# Valve_with_oc.net
KiCad netlist of a schematic drawn in EAGLE
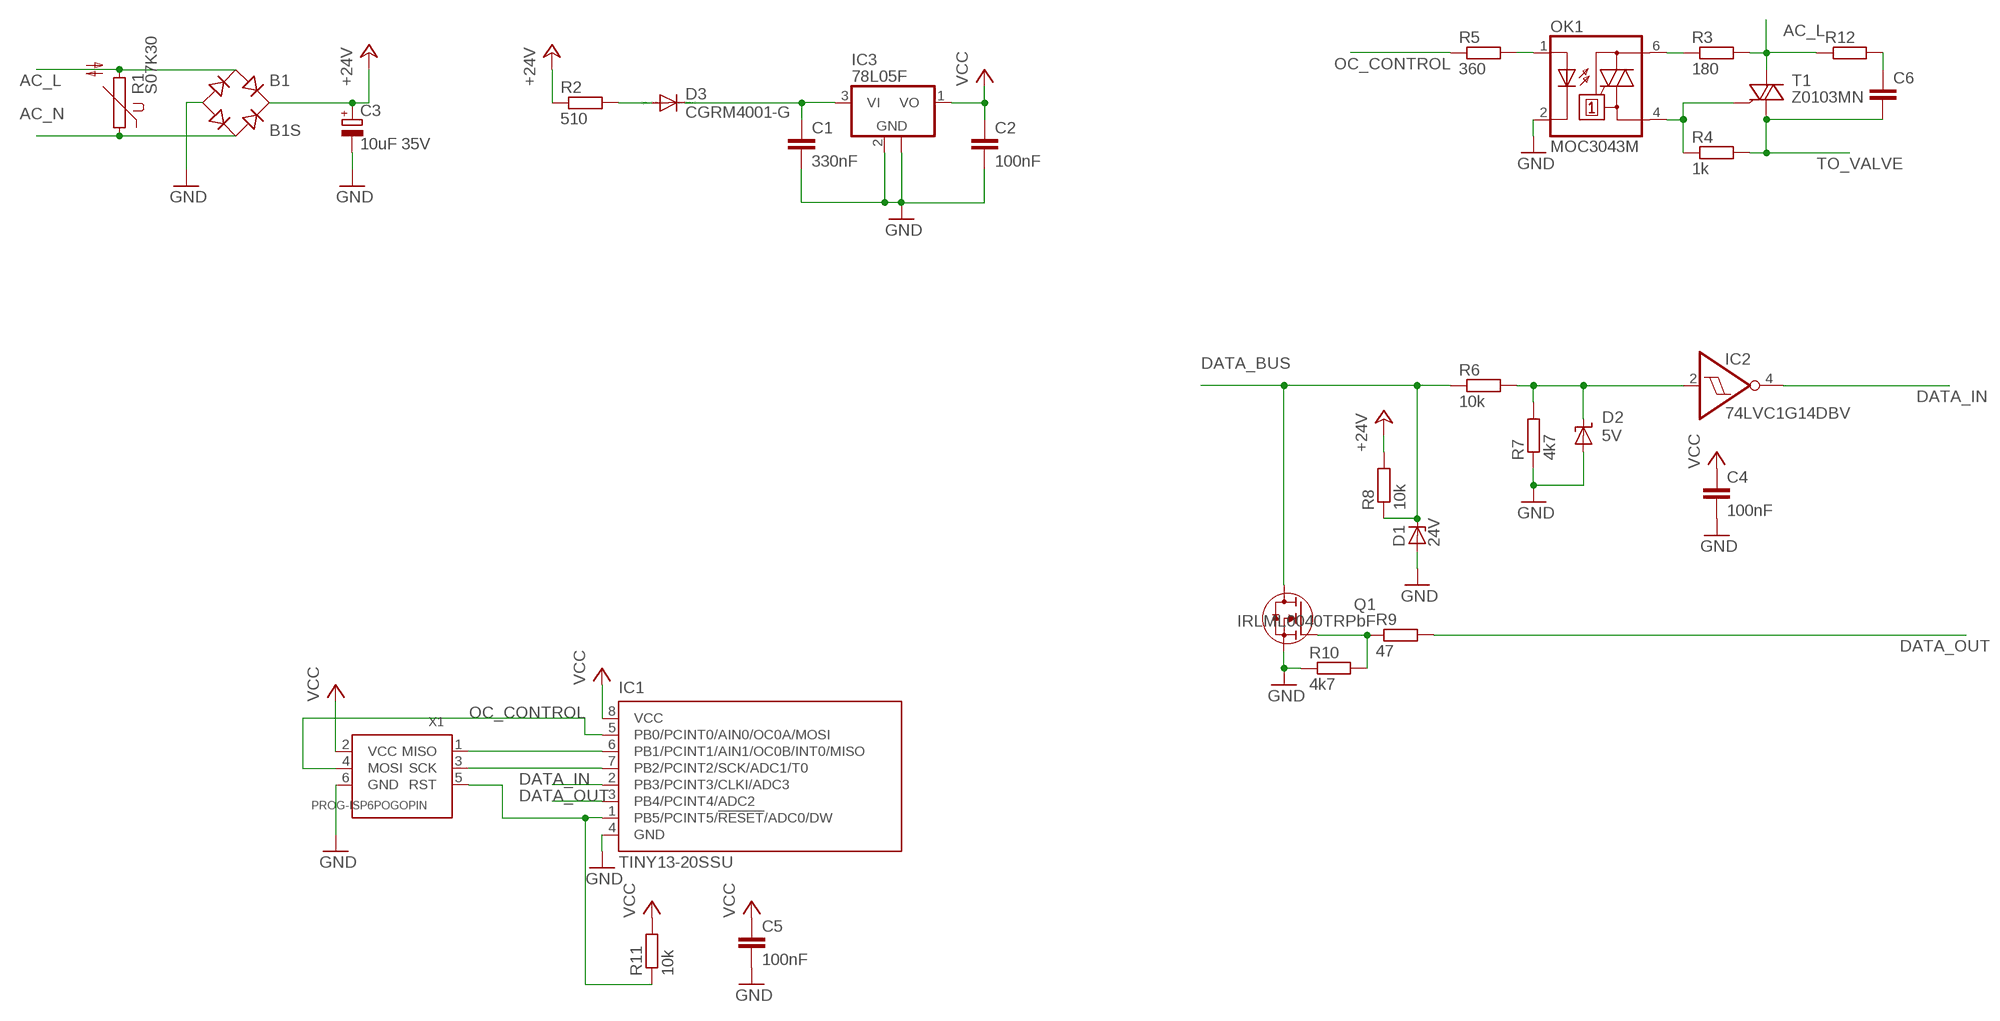
[diagram p0: schematic, sheet 1]

(export (version "E")
  (design (tool "Eeschema 10.0.6"))
  (components
    (comp (ref "B1")
      (value "B1S")
      (footprint "eagle-import:MBS")
      (libsource (lib "eagle-import") (part "BS1"))
    )
    (comp (ref "C1")
      (value "330nF")
      (footprint "eagle-import:C0805K")
      (libsource (lib "eagle-import") (part "C-EUC0805K"))
    )
    (comp (ref "C2")
      (value "100nF")
      (footprint "eagle-import:C0805K")
      (libsource (lib "eagle-import") (part "C-EUC0805K"))
    )
    (comp (ref "C3")
      (value "10uF 35V")
      (footprint "eagle-import:C_6032-28R")
      (libsource (lib "eagle-import") (part "CPOL-EUC/6032-28R"))
    )
    (comp (ref "C4")
      (value "100nF")
      (footprint "eagle-import:C0805K")
      (libsource (lib "eagle-import") (part "C-EUC0805K"))
    )
    (comp (ref "C5")
      (value "100nF")
      (footprint "eagle-import:C0805K")
      (libsource (lib "eagle-import") (part "C-EUC0805K"))
    )
    (comp (ref "C6")
      (value "C-EUC0805K")
      (footprint "eagle-import:C0805K")
      (libsource (lib "eagle-import") (part "C-EUC0805K"))
    )
    (comp (ref "D1")
      (value "24V")
      (footprint "eagle-import:SOT23")
      (libsource (lib "eagle-import") (part "ZENER-DIODESOT23"))
    )
    (comp (ref "D2")
      (value "5V")
      (footprint "eagle-import:SOD123")
      (libsource (lib "eagle-import") (part "ZENER"))
    )
    (comp (ref "D3")
      (value "CGRM4001-G")
      (footprint "eagle-import:SOD-123_MINI-SMA")
      (libsource (lib "eagle-import") (part "CGRM400-G1"))
    )
    (comp (ref "IC1")
      (value "TINY13-20SSU")
      (footprint "eagle-import:8S1")
      (fields (field (name "MPN") "ATTINY13-20SSU"))
      (libsource (lib "eagle-import") (part "TINY13SSU-20"))
    )
    (comp (ref "IC2")
      (value "74LVC1G14DBV")
      (footprint "eagle-import:SOT23-5")
      (libsource (lib "eagle-import") (part "741G14DBVLVC"))
    )
    (comp (ref "IC3")
      (value "78L05F")
      (footprint "eagle-import:SOT89")
      (libsource (lib "eagle-import") (part "78LF05"))
    )
    (comp (ref "OK1")
      (value "MOC3043M")
      (footprint "eagle-import:DIL06")
      (fields (field (name "MF") "FAIRCHILD SEMICONDUCTOR") (field (name "MPN") "MOC3043-M"))
      (libsource (lib "eagle-import") (part "MOC3043M"))
    )
    (comp (ref "Q1")
      (value "IRLML0040TRPbF")
      (footprint "eagle-import:SOT-23-GSD")
      (libsource (lib "eagle-import") (part "SI2302"))
    )
    (comp (ref "R1")
      (value "S07K30")
      (footprint "eagle-import:S07K40")
      (libsource (lib "eagle-import") (part "S07K40"))
    )
    (comp (ref "R2")
      (value "510")
      (footprint "eagle-import:R2512")
      (libsource (lib "eagle-import") (part "R-EU_R2512"))
    )
    (comp (ref "R3")
      (value "180")
      (footprint "eagle-import:R0805")
      (libsource (lib "eagle-import") (part "R-EU_R0805"))
    )
    (comp (ref "R4")
      (value "1k")
      (footprint "eagle-import:R0805")
      (libsource (lib "eagle-import") (part "R-EU_R0805"))
    )
    (comp (ref "R5")
      (value "360")
      (footprint "eagle-import:R0805")
      (libsource (lib "eagle-import") (part "R-EU_R0805"))
    )
    (comp (ref "R6")
      (value "10k")
      (footprint "eagle-import:R0805")
      (libsource (lib "eagle-import") (part "R-EU_R0805"))
    )
    (comp (ref "R7")
      (value "4k7")
      (footprint "eagle-import:R0805")
      (libsource (lib "eagle-import") (part "R-EU_R0805"))
    )
    (comp (ref "R8")
      (value "10k")
      (footprint "eagle-import:R0805")
      (libsource (lib "eagle-import") (part "R-EU_R0805"))
    )
    (comp (ref "R9")
      (value "47")
      (footprint "eagle-import:R0805")
      (libsource (lib "eagle-import") (part "R-EU_R0805"))
    )
    (comp (ref "R10")
      (value "4k7")
      (footprint "eagle-import:R0805")
      (libsource (lib "eagle-import") (part "R-EU_R0805"))
    )
    (comp (ref "R11")
      (value "10k")
      (footprint "eagle-import:R0805")
      (libsource (lib "eagle-import") (part "R-EU_R0805"))
    )
    (comp (ref "R12")
      (value "R-EU_R0805")
      (footprint "eagle-import:R0805")
      (libsource (lib "eagle-import") (part "R-EU_R0805"))
    )
    (comp (ref "T1")
      (value "Z0103MN")
      (footprint "eagle-import:SOT223")
      (libsource (lib "eagle-import") (part "Z0103MN"))
    )
    (comp (ref "X1")
      (value "PROG-ISP6POGOPIN")
      (footprint "eagle-import:PROG_POGOPIN")
      (libsource (lib "eagle-import") (part "PROG-ISP6POGOPIN"))
    )
  )
  (nets
    (net (code "1") (name "+24V") (class "Default")
      (node (ref "B1") (pin "+") (pinfunction "+_+") (pintype "passive"))
      (node (ref "C3") (pin "+") (pinfunction "+_+") (pintype "passive"))
      (node (ref "R2") (pin "1") (pinfunction "1_1") (pintype "passive"))
      (node (ref "R8") (pin "2") (pinfunction "2_2") (pintype "passive"))
    )
    (net (code "2") (name "/AC_L") (class "Default")
      (node (ref "B1") (pin "AC1") (pinfunction "AC1_AC1") (pintype "passive"))
      (node (ref "R1") (pin "2") (pinfunction "2_2") (pintype "passive"))
      (node (ref "R12") (pin "1") (pinfunction "1_1") (pintype "passive"))
      (node (ref "R3") (pin "2") (pinfunction "2_2") (pintype "passive"))
      (node (ref "T1") (pin "2") (pinfunction "A2_2") (pintype "passive"))
      (node (ref "T1") (pin "4") (pinfunction "A2_4") (pintype "passive"))
    )
    (net (code "3") (name "/AC_N") (class "Default")
      (node (ref "B1") (pin "AC2") (pinfunction "AC2_AC2") (pintype "passive"))
      (node (ref "R1") (pin "1") (pinfunction "1_1") (pintype "passive"))
    )
    (net (code "4") (name "/DATA_BUS") (class "Default")
      (node (ref "D1") (pin "3") (pinfunction "C_3") (pintype "passive"))
      (node (ref "Q1") (pin "D") (pinfunction "D_D") (pintype "passive"))
      (node (ref "R6") (pin "1") (pinfunction "1_1") (pintype "passive"))
      (node (ref "R8") (pin "1") (pinfunction "1_1") (pintype "passive"))
    )
    (net (code "5") (name "/DATA_IN") (class "Default")
      (node (ref "IC1") (pin "2") (pinfunction "PB3/PCINT3/CLKI/ADC3_2") (pintype "bidirectional"))
      (node (ref "IC2") (pin "4") (pinfunction "O_4") (pintype "output"))
    )
    (net (code "6") (name "/DATA_OUT") (class "Default")
      (node (ref "IC1") (pin "3") (pinfunction "PB4/PCINT4/ADC2_3") (pintype "bidirectional"))
      (node (ref "R9") (pin "2") (pinfunction "2_2") (pintype "passive"))
    )
    (net (code "7") (name "/OC_CONTROL") (class "Default")
      (node (ref "IC1") (pin "5") (pinfunction "PB0/PCINT0/AIN0/OC0A/MOSI_5") (pintype "bidirectional"))
      (node (ref "R5") (pin "1") (pinfunction "1_1") (pintype "passive"))
      (node (ref "X1") (pin "4") (pinfunction "MOSI_4") (pintype "bidirectional"))
    )
    (net (code "8") (name "/TO_VALVE") (class "Default")
      (node (ref "C6") (pin "2") (pinfunction "2_2") (pintype "passive"))
      (node (ref "R4") (pin "2") (pinfunction "2_2") (pintype "passive"))
      (node (ref "T1") (pin "1") (pinfunction "A1_1") (pintype "passive"))
    )
    (net (code "9") (name "GND") (class "Default")
      (node (ref "B1") (pin "-") (pinfunction "-_-") (pintype "passive"))
      (node (ref "C1") (pin "2") (pinfunction "2_2") (pintype "passive"))
      (node (ref "C2") (pin "2") (pinfunction "2_2") (pintype "passive"))
      (node (ref "C3") (pin "-") (pinfunction "-_-") (pintype "passive"))
      (node (ref "C4") (pin "2") (pinfunction "2_2") (pintype "passive"))
      (node (ref "C5") (pin "2") (pinfunction "2_2") (pintype "passive"))
      (node (ref "D1") (pin "1") (pinfunction "A_1") (pintype "passive"))
      (node (ref "D2") (pin "A") (pinfunction "A_A") (pintype "passive"))
      (node (ref "IC1") (pin "4") (pinfunction "GND_4") (pintype "power_in"))
      (node (ref "IC3") (pin "2") (pinfunction "GND_2") (pintype "passive"))
      (node (ref "IC3") (pin "2@1") (pinfunction "GND_2@1") (pintype "passive"))
      (node (ref "OK1") (pin "2") (pinfunction "C_2") (pintype "passive"))
      (node (ref "Q1") (pin "S") (pinfunction "S_S") (pintype "passive"))
      (node (ref "R10") (pin "1") (pinfunction "1_1") (pintype "passive"))
      (node (ref "R7") (pin "1") (pinfunction "1_1") (pintype "passive"))
      (node (ref "X1") (pin "6") (pinfunction "GND_6") (pintype "power_in"))
    )
    (net (code "10") (name "Net-(C6-Pad1)") (class "Default")
      (node (ref "C6") (pin "1") (pinfunction "1_1") (pintype "passive"))
      (node (ref "R12") (pin "2") (pinfunction "2_2") (pintype "passive"))
    )
    (net (code "11") (name "Net-(D3-PadA)") (class "Default")
      (node (ref "D3") (pin "A") (pinfunction "A_A") (pintype "passive"))
      (node (ref "R2") (pin "2") (pinfunction "2_2") (pintype "passive"))
    )
    (net (code "12") (name "Net-(IC1-PB1{slash}PCINT1{slash}AIN1{slash}OC0B{slash}INT0{slash}MISO)") (class "Default")
      (node (ref "IC1") (pin "6") (pinfunction "PB1/PCINT1/AIN1/OC0B/INT0/MISO_6") (pintype "bidirectional"))
      (node (ref "X1") (pin "1") (pinfunction "MISO_1") (pintype "bidirectional"))
    )
    (net (code "13") (name "Net-(IC1-PB2{slash}PCINT2{slash}SCK{slash}ADC1{slash}T0)") (class "Default")
      (node (ref "IC1") (pin "7") (pinfunction "PB2/PCINT2/SCK/ADC1/T0_7") (pintype "bidirectional"))
      (node (ref "X1") (pin "3") (pinfunction "SCK_3") (pintype "bidirectional"))
    )
    (net (code "14") (name "Net-(IC1-PB5{slash}PCINT5{slash}~{RESET}{slash}ADC0{slash}DW)") (class "Default")
      (node (ref "IC1") (pin "1") (pinfunction "PB5/PCINT5/~{RESET}/ADC0/DW_1") (pintype "bidirectional"))
      (node (ref "R11") (pin "1") (pinfunction "1_1") (pintype "passive"))
      (node (ref "X1") (pin "5") (pinfunction "RST_5") (pintype "bidirectional"))
    )
    (net (code "15") (name "Net-(IC2A-I)") (class "Default")
      (node (ref "D2") (pin "C") (pinfunction "C_C") (pintype "passive"))
      (node (ref "IC2") (pin "2") (pinfunction "I_2") (pintype "input"))
      (node (ref "R6") (pin "2") (pinfunction "2_2") (pintype "passive"))
      (node (ref "R7") (pin "2") (pinfunction "2_2") (pintype "passive"))
    )
    (net (code "16") (name "Net-(IC3-VI)") (class "Default")
      (node (ref "C1") (pin "1") (pinfunction "1_1") (pintype "passive"))
      (node (ref "D3") (pin "C") (pinfunction "C_C") (pintype "passive"))
      (node (ref "IC3") (pin "3") (pinfunction "VI_3") (pintype "input"))
    )
    (net (code "17") (name "Net-(OK1-A)") (class "Default")
      (node (ref "OK1") (pin "1") (pinfunction "A_1") (pintype "passive"))
      (node (ref "R5") (pin "2") (pinfunction "2_2") (pintype "passive"))
    )
    (net (code "18") (name "Net-(OK1-A1)") (class "Default")
      (node (ref "OK1") (pin "4") (pinfunction "A1_4") (pintype "passive"))
      (node (ref "R4") (pin "1") (pinfunction "1_1") (pintype "passive"))
      (node (ref "T1") (pin "3") (pinfunction "G_3") (pintype "passive"))
    )
    (net (code "19") (name "Net-(OK1-A2)") (class "Default")
      (node (ref "OK1") (pin "6") (pinfunction "A2_6") (pintype "passive"))
      (node (ref "R3") (pin "1") (pinfunction "1_1") (pintype "passive"))
    )
    (net (code "20") (name "Net-(Q1-PadG)") (class "Default")
      (node (ref "Q1") (pin "G") (pinfunction "G_G") (pintype "passive"))
      (node (ref "R10") (pin "2") (pinfunction "2_2") (pintype "passive"))
      (node (ref "R9") (pin "1") (pinfunction "1_1") (pintype "passive"))
    )
    (net (code "21") (name "VCC") (class "Default")
      (node (ref "C2") (pin "1") (pinfunction "1_1") (pintype "passive"))
      (node (ref "C4") (pin "1") (pinfunction "1_1") (pintype "passive"))
      (node (ref "C5") (pin "1") (pinfunction "1_1") (pintype "passive"))
      (node (ref "IC1") (pin "8") (pinfunction "VCC_8") (pintype "power_in"))
      (node (ref "IC3") (pin "1") (pinfunction "VO_1") (pintype "passive"))
      (node (ref "R11") (pin "2") (pinfunction "2_2") (pintype "passive"))
      (node (ref "X1") (pin "2") (pinfunction "VCC_2") (pintype "bidirectional"))
    )
  )
)
